# MCU_Unit.net
KiCad netlist of a schematic drawn in Altium Designer
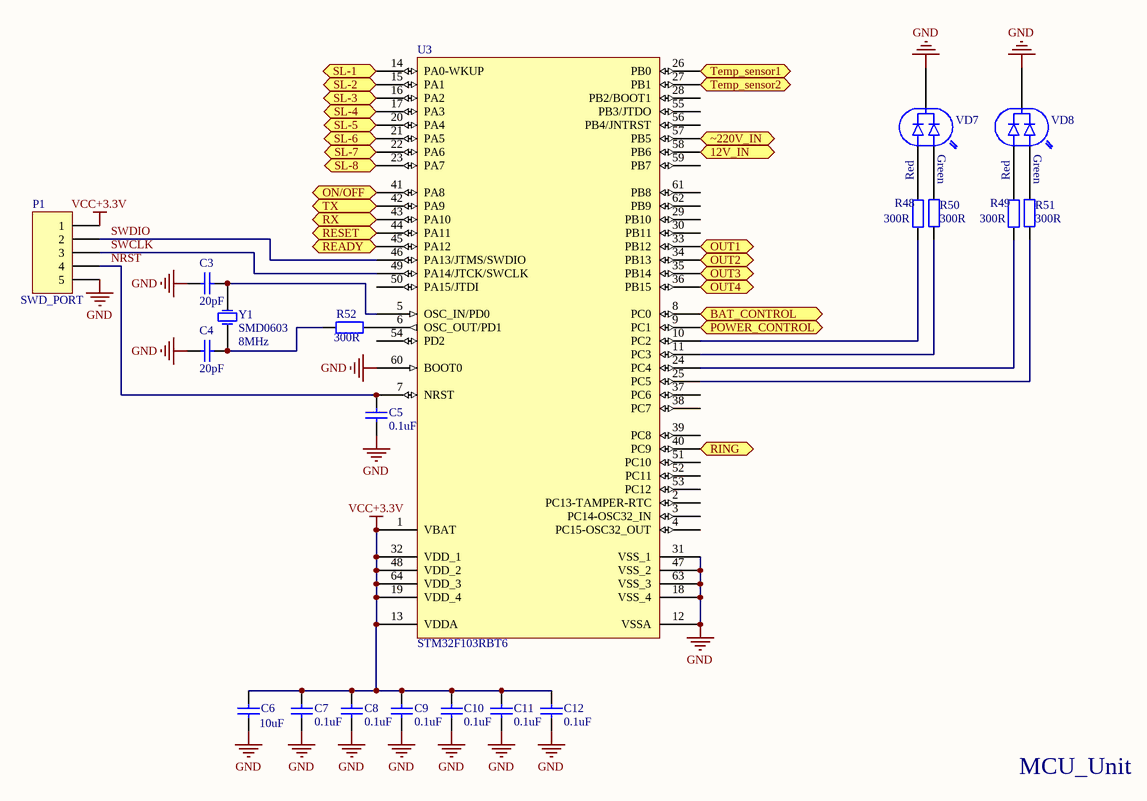
[diagram p0: MCU_Unit.SchDoc]

(export (version "E")
  (design (tool "Eeschema 10.0.6"))
  (components
    (comp (ref "C3")
      (value "20pF")
      (footprint "C0603")
      (description "Capasitor_SMD_0808/")
      (fields (field (name "Comment") "CAP_SMD"))
      (libsource (lib "NEW") (part "Capasitor_SMD_0805"))
    )
    (comp (ref "C4")
      (value "20pF")
      (footprint "C0603")
      (description "Capasitor_SMD_0808/")
      (fields (field (name "Comment") "CAP_SMD"))
      (libsource (lib "NEW") (part "Capasitor_SMD_0805"))
    )
    (comp (ref "C5")
      (value "0.1uF")
      (footprint "C0603")
      (description "Capasitor_SMD_0808/")
      (fields (field (name "Comment") "CAP_SMD"))
      (libsource (lib "NEW") (part "Capasitor_SMD_0805"))
    )
    (comp (ref "C6")
      (value "10uF")
      (footprint "C1210")
      (description "Capacitor (Semiconductor SIM Model)")
      (fields (field (name "Comment") "Cap Semi") (field (name "PUBLISHER") "Altium Limited"))
      (libsource (lib "Miscellaneous Devices") (part "Cap Semi"))
    )
    (comp (ref "C7")
      (value "0.1uF")
      (footprint "C0603")
      (description "Capasitor_SMD_0808/")
      (fields (field (name "Comment") "CAP_SMD"))
      (libsource (lib "NEW") (part "Capasitor_SMD_0805"))
    )
    (comp (ref "C8")
      (value "0.1uF")
      (footprint "C0603")
      (description "Capasitor_SMD_0808/")
      (fields (field (name "Comment") "CAP_SMD"))
      (libsource (lib "NEW") (part "Capasitor_SMD_0805"))
    )
    (comp (ref "C9")
      (value "0.1uF")
      (footprint "C0603")
      (description "Capasitor_SMD_0808/")
      (fields (field (name "Comment") "CAP_SMD"))
      (libsource (lib "NEW") (part "Capasitor_SMD_0805"))
    )
    (comp (ref "C10")
      (value "0.1uF")
      (footprint "C0603")
      (description "Capasitor_SMD_0808/")
      (fields (field (name "Comment") "CAP_SMD"))
      (libsource (lib "NEW") (part "Capasitor_SMD_0805"))
    )
    (comp (ref "C11")
      (value "0.1uF")
      (footprint "C0603")
      (description "Capasitor_SMD_0808/")
      (fields (field (name "Comment") "CAP_SMD"))
      (libsource (lib "NEW") (part "Capasitor_SMD_0805"))
    )
    (comp (ref "C12")
      (value "0.1uF")
      (footprint "C0603")
      (description "Capasitor_SMD_0808/")
      (fields (field (name "Comment") "CAP_SMD"))
      (libsource (lib "NEW") (part "Capasitor_SMD_0805"))
    )
    (comp (ref "P1")
      (value "SWD_PORT")
      (footprint "HDR1X5")
      (description "Header, 5-Pin")
      (fields (field (name "PUBLISHER") "Altium Limited"))
      (libsource (lib "Miscellaneous Connectors") (part "Header 5"))
    )
    (comp (ref "R48")
      (value "300R")
      (footprint "C0603")
      (description "Resistor")
      (fields (field (name "Comment") "RES_SMD"))
      (libsource (lib "NEW") (part "RES"))
    )
    (comp (ref "R49")
      (value "300R")
      (footprint "C0603")
      (description "Resistor")
      (fields (field (name "Comment") "RES_SMD"))
      (libsource (lib "NEW") (part "RES"))
    )
    (comp (ref "R50")
      (value "300R")
      (footprint "C0603")
      (description "Resistor")
      (fields (field (name "Comment") "RES_SMD"))
      (libsource (lib "NEW") (part "RES"))
    )
    (comp (ref "R51")
      (value "300R")
      (footprint "C0603")
      (description "Resistor")
      (fields (field (name "Comment") "RES_SMD"))
      (libsource (lib "NEW") (part "RES"))
    )
    (comp (ref "R52")
      (value "300R")
      (footprint "C0603")
      (description "Resistor")
      (fields (field (name "Comment") "RES_SMD"))
      (libsource (lib "") (part "RES_1"))
    )
    (comp (ref "U3")
      (value "STM32F103RBT6")
      (footprint "LQFP64_N")
      (description "STM32 ARM-based 32-bit MCU with 128 Kbytes Flash, 64-pin LQFP, Industrial Temperature")
      (fields (field (name "PUBLISHER") "Altium Limited"))
      (libsource (lib "ST Microcontroller 32-Bit STM32") (part "STM32F103RBT6"))
    )
    (comp (ref "VD7")
      (value "LIGHTDIODE2")
      (footprint "LIGHTDIODE2")
      (libsource (lib "NEW") (part "LIGHTDIODE2"))
    )
    (comp (ref "VD8")
      (value "LIGHTDIODE2")
      (footprint "LIGHTDIODE2")
      (libsource (lib "NEW") (part "LIGHTDIODE2"))
    )
    (comp (ref "Y1")
      (value "SMD0603")
      (footprint "Quartz_SMD0603")
      (fields (field (name "ALTIUM_UNNAMED_1") "8MHz"))
      (libsource (lib "NEW") (part "Quartz_SMD"))
    )
  )
  (nets
    (net (code "1") (name "/12V_IN") (class "Default")
      (node (ref "U3") (pin "58") (pinfunction "PB6_58") (pintype "bidirectional"))
    )
    (net (code "2") (name "/BAT_CONTROL") (class "Default")
      (node (ref "U3") (pin "8") (pinfunction "PC0_8") (pintype "bidirectional"))
    )
    (net (code "3") (name "/NRST") (class "Default")
      (node (ref "C5") (pin "1") (pinfunction "1_1") (pintype "passive"))
      (node (ref "P1") (pin "4") (pinfunction "4_4") (pintype "passive"))
      (node (ref "U3") (pin "7") (pinfunction "NRST_7") (pintype "bidirectional"))
    )
    (net (code "4") (name "/ON{slash}OFF") (class "Default")
      (node (ref "U3") (pin "41") (pinfunction "PA8_41") (pintype "bidirectional"))
    )
    (net (code "5") (name "/OUT1") (class "Default")
      (node (ref "U3") (pin "33") (pinfunction "PB12_33") (pintype "bidirectional"))
    )
    (net (code "6") (name "/OUT2") (class "Default")
      (node (ref "U3") (pin "34") (pinfunction "PB13_34") (pintype "bidirectional"))
    )
    (net (code "7") (name "/OUT3") (class "Default")
      (node (ref "U3") (pin "35") (pinfunction "PB14_35") (pintype "bidirectional"))
    )
    (net (code "8") (name "/OUT4") (class "Default")
      (node (ref "U3") (pin "36") (pinfunction "PB15_36") (pintype "bidirectional"))
    )
    (net (code "9") (name "/POWER_CONTROL") (class "Default")
      (node (ref "U3") (pin "9") (pinfunction "PC1_9") (pintype "bidirectional"))
    )
    (net (code "10") (name "/READY") (class "Default")
      (node (ref "U3") (pin "45") (pinfunction "PA12_45") (pintype "bidirectional"))
    )
    (net (code "11") (name "/RESET") (class "Default")
      (node (ref "U3") (pin "44") (pinfunction "PA11_44") (pintype "bidirectional"))
    )
    (net (code "12") (name "/RING") (class "Default")
      (node (ref "U3") (pin "40") (pinfunction "PC9_40") (pintype "bidirectional"))
    )
    (net (code "13") (name "/RX") (class "Default")
      (node (ref "U3") (pin "43") (pinfunction "PA10_43") (pintype "bidirectional"))
    )
    (net (code "14") (name "/SL-1") (class "Default")
      (node (ref "U3") (pin "14") (pinfunction "PA0-WKUP_14") (pintype "bidirectional"))
    )
    (net (code "15") (name "/SL-2") (class "Default")
      (node (ref "U3") (pin "15") (pinfunction "PA1_15") (pintype "bidirectional"))
    )
    (net (code "16") (name "/SL-3") (class "Default")
      (node (ref "U3") (pin "16") (pinfunction "PA2_16") (pintype "bidirectional"))
    )
    (net (code "17") (name "/SL-4") (class "Default")
      (node (ref "U3") (pin "17") (pinfunction "PA3_17") (pintype "bidirectional"))
    )
    (net (code "18") (name "/SL-5") (class "Default")
      (node (ref "U3") (pin "20") (pinfunction "PA4_20") (pintype "bidirectional"))
    )
    (net (code "19") (name "/SL-6") (class "Default")
      (node (ref "U3") (pin "21") (pinfunction "PA5_21") (pintype "bidirectional"))
    )
    (net (code "20") (name "/SL-7") (class "Default")
      (node (ref "U3") (pin "22") (pinfunction "PA6_22") (pintype "bidirectional"))
    )
    (net (code "21") (name "/SL-8") (class "Default")
      (node (ref "U3") (pin "23") (pinfunction "PA7_23") (pintype "bidirectional"))
    )
    (net (code "22") (name "/SWCLK") (class "Default")
      (node (ref "P1") (pin "3") (pinfunction "3_3") (pintype "passive"))
      (node (ref "U3") (pin "49") (pinfunction "PA14/JTCK/SWCLK_49") (pintype "bidirectional"))
    )
    (net (code "23") (name "/SWDIO") (class "Default")
      (node (ref "P1") (pin "2") (pinfunction "2_2") (pintype "passive"))
      (node (ref "U3") (pin "46") (pinfunction "PA13/JTMS/SWDIO_46") (pintype "bidirectional"))
    )
    (net (code "24") (name "/TX") (class "Default")
      (node (ref "U3") (pin "42") (pinfunction "PA9_42") (pintype "bidirectional"))
    )
    (net (code "25") (name "/Temp_sensor1") (class "Default")
      (node (ref "U3") (pin "26") (pinfunction "PB0_26") (pintype "bidirectional"))
    )
    (net (code "26") (name "/Temp_sensor2") (class "Default")
      (node (ref "U3") (pin "27") (pinfunction "PB1_27") (pintype "bidirectional"))
    )
    (net (code "27") (name "/~220V_IN") (class "Default")
      (node (ref "U3") (pin "57") (pinfunction "PB5_57") (pintype "bidirectional"))
    )
    (net (code "28") (name "GND") (class "Default")
      (node (ref "C10") (pin "2") (pinfunction "2_2") (pintype "passive"))
      (node (ref "C11") (pin "2") (pinfunction "2_2") (pintype "passive"))
      (node (ref "C12") (pin "2") (pinfunction "2_2") (pintype "passive"))
      (node (ref "C3") (pin "1") (pinfunction "1_1") (pintype "passive"))
      (node (ref "C4") (pin "1") (pinfunction "1_1") (pintype "passive"))
      (node (ref "C5") (pin "2") (pinfunction "2_2") (pintype "passive"))
      (node (ref "C6") (pin "1") (pinfunction "1_1") (pintype "passive"))
      (node (ref "C7") (pin "2") (pinfunction "2_2") (pintype "passive"))
      (node (ref "C8") (pin "2") (pinfunction "2_2") (pintype "passive"))
      (node (ref "C9") (pin "2") (pinfunction "2_2") (pintype "passive"))
      (node (ref "P1") (pin "5") (pinfunction "5_5") (pintype "passive"))
      (node (ref "U3") (pin "12") (pinfunction "VSSA_12") (pintype "power_in"))
      (node (ref "U3") (pin "18") (pinfunction "VSS_4_18") (pintype "power_in"))
      (node (ref "U3") (pin "31") (pinfunction "VSS_1_31") (pintype "power_in"))
      (node (ref "U3") (pin "47") (pinfunction "VSS_2_47") (pintype "power_in"))
      (node (ref "U3") (pin "60") (pinfunction "BOOT0_60") (pintype "input"))
      (node (ref "U3") (pin "63") (pinfunction "VSS_3_63") (pintype "power_in"))
      (node (ref "VD7") (pin "1") (pinfunction "1_1") (pintype "passive"))
      (node (ref "VD8") (pin "1") (pinfunction "1_1") (pintype "passive"))
    )
    (net (code "29") (name "Net-(R48-Pad2)") (class "Default")
      (node (ref "R48") (pin "2") (pinfunction "2_2") (pintype "passive"))
      (node (ref "VD7") (pin "3") (pinfunction "3_3") (pintype "passive"))
    )
    (net (code "30") (name "Net-(R49-Pad2)") (class "Default")
      (node (ref "R49") (pin "2") (pinfunction "2_2") (pintype "passive"))
      (node (ref "VD8") (pin "3") (pinfunction "3_3") (pintype "passive"))
    )
    (net (code "31") (name "Net-(R50-Pad2)") (class "Default")
      (node (ref "R50") (pin "2") (pinfunction "2_2") (pintype "passive"))
      (node (ref "VD7") (pin "2") (pinfunction "2_2") (pintype "passive"))
    )
    (net (code "32") (name "Net-(R51-Pad2)") (class "Default")
      (node (ref "R51") (pin "2") (pinfunction "2_2") (pintype "passive"))
      (node (ref "VD8") (pin "2") (pinfunction "2_2") (pintype "passive"))
    )
    (net (code "33") (name "Net-(U3-OSC_IN{slash}PD0)") (class "Default")
      (node (ref "C3") (pin "2") (pinfunction "2_2") (pintype "passive"))
      (node (ref "U3") (pin "5") (pinfunction "OSC_IN/PD0_5") (pintype "input"))
      (node (ref "Y1") (pin "3") (pinfunction "OSC2_3") (pintype "passive"))
    )
    (net (code "34") (name "Net-(U3-OSC_OUT{slash}PD1)") (class "Default")
      (node (ref "R52") (pin "2") (pinfunction "2_2") (pintype "passive"))
      (node (ref "U3") (pin "6") (pinfunction "OSC_OUT/PD1_6") (pintype "output"))
    )
    (net (code "35") (name "Net-(U3-PC2)") (class "Default")
      (node (ref "R48") (pin "1") (pinfunction "1_1") (pintype "passive"))
      (node (ref "U3") (pin "10") (pinfunction "PC2_10") (pintype "bidirectional"))
    )
    (net (code "36") (name "Net-(U3-PC3)") (class "Default")
      (node (ref "R50") (pin "1") (pinfunction "1_1") (pintype "passive"))
      (node (ref "U3") (pin "11") (pinfunction "PC3_11") (pintype "bidirectional"))
    )
    (net (code "37") (name "Net-(U3-PC4)") (class "Default")
      (node (ref "R49") (pin "1") (pinfunction "1_1") (pintype "passive"))
      (node (ref "U3") (pin "24") (pinfunction "PC4_24") (pintype "bidirectional"))
    )
    (net (code "38") (name "Net-(U3-PC5)") (class "Default")
      (node (ref "R51") (pin "1") (pinfunction "1_1") (pintype "passive"))
      (node (ref "U3") (pin "25") (pinfunction "PC5_25") (pintype "bidirectional"))
    )
    (net (code "39") (name "Net-(Y1-OSC1)") (class "Default")
      (node (ref "C4") (pin "2") (pinfunction "2_2") (pintype "passive"))
      (node (ref "R52") (pin "1") (pinfunction "1_1") (pintype "passive"))
      (node (ref "Y1") (pin "1") (pinfunction "OSC1_1") (pintype "passive"))
    )
    (net (code "40") (name "VCC+3.3V") (class "Default")
      (node (ref "C10") (pin "1") (pinfunction "1_1") (pintype "passive"))
      (node (ref "C11") (pin "1") (pinfunction "1_1") (pintype "passive"))
      (node (ref "C12") (pin "1") (pinfunction "1_1") (pintype "passive"))
      (node (ref "C6") (pin "2") (pinfunction "2_2") (pintype "passive"))
      (node (ref "C7") (pin "1") (pinfunction "1_1") (pintype "passive"))
      (node (ref "C8") (pin "1") (pinfunction "1_1") (pintype "passive"))
      (node (ref "C9") (pin "1") (pinfunction "1_1") (pintype "passive"))
      (node (ref "P1") (pin "1") (pinfunction "1_1") (pintype "passive"))
      (node (ref "U3") (pin "1") (pinfunction "VBAT_1") (pintype "power_in"))
      (node (ref "U3") (pin "13") (pinfunction "VDDA_13") (pintype "power_in"))
      (node (ref "U3") (pin "19") (pinfunction "VDD_4_19") (pintype "power_in"))
      (node (ref "U3") (pin "32") (pinfunction "VDD_1_32") (pintype "power_in"))
      (node (ref "U3") (pin "48") (pinfunction "VDD_2_48") (pintype "power_in"))
      (node (ref "U3") (pin "64") (pinfunction "VDD_3_64") (pintype "power_in"))
    )
    (net (code "41") (name "unconnected-(U3-PA15{slash}JTDI-Pad50)") (class "Default")
      (node (ref "U3") (pin "50") (pinfunction "PA15/JTDI_50") (pintype "bidirectional"))
    )
    (net (code "42") (name "unconnected-(U3-PB2{slash}BOOT1-Pad28)") (class "Default")
      (node (ref "U3") (pin "28") (pinfunction "PB2/BOOT1_28") (pintype "bidirectional"))
    )
    (net (code "43") (name "unconnected-(U3-PB3{slash}JTDO-Pad55)") (class "Default")
      (node (ref "U3") (pin "55") (pinfunction "PB3/JTDO_55") (pintype "bidirectional"))
    )
    (net (code "44") (name "unconnected-(U3-PB4{slash}JNTRST-Pad56)") (class "Default")
      (node (ref "U3") (pin "56") (pinfunction "PB4/JNTRST_56") (pintype "bidirectional"))
    )
    (net (code "45") (name "unconnected-(U3-PB7-Pad59)") (class "Default")
      (node (ref "U3") (pin "59") (pinfunction "PB7_59") (pintype "bidirectional"))
    )
    (net (code "46") (name "unconnected-(U3-PB8-Pad61)") (class "Default")
      (node (ref "U3") (pin "61") (pinfunction "PB8_61") (pintype "bidirectional"))
    )
    (net (code "47") (name "unconnected-(U3-PB9-Pad62)") (class "Default")
      (node (ref "U3") (pin "62") (pinfunction "PB9_62") (pintype "bidirectional"))
    )
    (net (code "48") (name "unconnected-(U3-PB10-Pad29)") (class "Default")
      (node (ref "U3") (pin "29") (pinfunction "PB10_29") (pintype "bidirectional"))
    )
    (net (code "49") (name "unconnected-(U3-PB11-Pad30)") (class "Default")
      (node (ref "U3") (pin "30") (pinfunction "PB11_30") (pintype "bidirectional"))
    )
    (net (code "50") (name "unconnected-(U3-PC6-Pad37)") (class "Default")
      (node (ref "U3") (pin "37") (pinfunction "PC6_37") (pintype "bidirectional"))
    )
    (net (code "51") (name "unconnected-(U3-PC7-Pad38)") (class "Default")
      (node (ref "U3") (pin "38") (pinfunction "PC7_38") (pintype "bidirectional"))
    )
    (net (code "52") (name "unconnected-(U3-PC8-Pad39)") (class "Default")
      (node (ref "U3") (pin "39") (pinfunction "PC8_39") (pintype "bidirectional"))
    )
    (net (code "53") (name "unconnected-(U3-PC10-Pad51)") (class "Default")
      (node (ref "U3") (pin "51") (pinfunction "PC10_51") (pintype "bidirectional"))
    )
    (net (code "54") (name "unconnected-(U3-PC11-Pad52)") (class "Default")
      (node (ref "U3") (pin "52") (pinfunction "PC11_52") (pintype "bidirectional"))
    )
    (net (code "55") (name "unconnected-(U3-PC12-Pad53)") (class "Default")
      (node (ref "U3") (pin "53") (pinfunction "PC12_53") (pintype "bidirectional"))
    )
    (net (code "56") (name "unconnected-(U3-PC13-TAMPER-RTC-Pad2)") (class "Default")
      (node (ref "U3") (pin "2") (pinfunction "PC13-TAMPER-RTC_2") (pintype "bidirectional"))
    )
    (net (code "57") (name "unconnected-(U3-PC14-OSC32_IN-Pad3)") (class "Default")
      (node (ref "U3") (pin "3") (pinfunction "PC14-OSC32_IN_3") (pintype "bidirectional"))
    )
    (net (code "58") (name "unconnected-(U3-PC15-OSC32_OUT-Pad4)") (class "Default")
      (node (ref "U3") (pin "4") (pinfunction "PC15-OSC32_OUT_4") (pintype "bidirectional"))
    )
    (net (code "59") (name "unconnected-(U3-PD2-Pad54)") (class "Default")
      (node (ref "U3") (pin "54") (pinfunction "PD2_54") (pintype "bidirectional"))
    )
  )
)
